# slouchpad_v1_leftpad.net
KiCad netlist of a schematic drawn in EAGLE
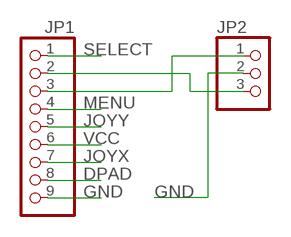
[diagram p0: schematic, sheet 1]
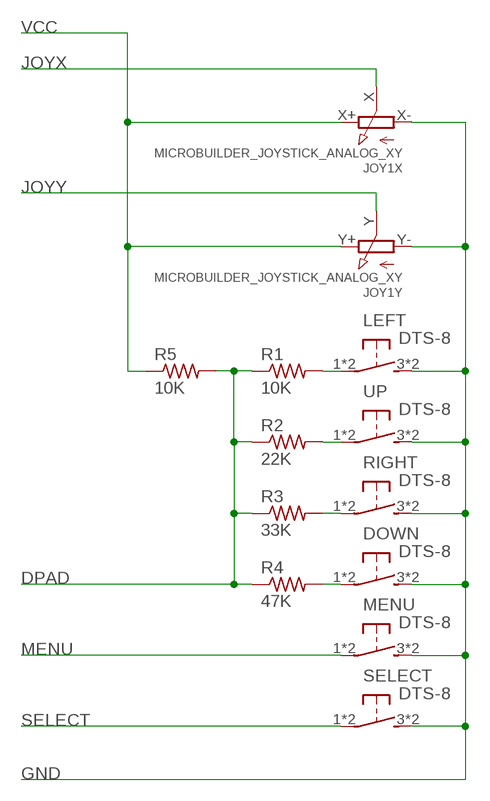
[diagram p1: schematic, sheet 2]

(export (version "E")
  (design (tool "Eeschema 10.0.6"))
  (components
    (comp (ref "DOWN")
      (value "DTS-8")
      (footprint "eagle-import:DTS-8")
      (libsource (lib "eagle-import") (part "DTS-8"))
    )
    (comp (ref "JOY1")
      (value "MICROBUILDER_JOYSTICK_ANALOG_XY")
      (footprint "eagle-import:MICROBUILDER_JOYSTICK_ANALOG_MINITHM")
      (libsource (lib "eagle-import") (part "MICROBUILDER_JOYSTICK_ANALOG_XY"))
    )
    (comp (ref "LEFT")
      (value "DTS-8")
      (footprint "eagle-import:DTS-8")
      (libsource (lib "eagle-import") (part "DTS-8"))
    )
    (comp (ref "MENU")
      (value "DTS-8")
      (footprint "eagle-import:DTS-8")
      (libsource (lib "eagle-import") (part "DTS-8"))
    )
    (comp (ref "R1")
      (value "10K")
      (footprint "eagle-import:0204_5")
      (libsource (lib "eagle-import") (part "R-US_0204/5"))
    )
    (comp (ref "R2")
      (value "22K")
      (footprint "eagle-import:0204_5")
      (libsource (lib "eagle-import") (part "R-US_0204/5"))
    )
    (comp (ref "R3")
      (value "33K")
      (footprint "eagle-import:0204_5")
      (libsource (lib "eagle-import") (part "R-US_0204/5"))
    )
    (comp (ref "R4")
      (value "47K")
      (footprint "eagle-import:0204_5")
      (libsource (lib "eagle-import") (part "R-US_0204/5"))
    )
    (comp (ref "R5")
      (value "10K")
      (footprint "eagle-import:0204_5")
      (libsource (lib "eagle-import") (part "R-US_0204/5"))
    )
    (comp (ref "RIGHT")
      (value "DTS-8")
      (footprint "eagle-import:DTS-8")
      (libsource (lib "eagle-import") (part "DTS-8"))
    )
    (comp (ref "SELECT")
      (value "DTS-8")
      (footprint "eagle-import:DTS-8")
      (libsource (lib "eagle-import") (part "DTS-8"))
    )
    (comp (ref "UP")
      (value "DTS-8")
      (footprint "eagle-import:DTS-8")
      (libsource (lib "eagle-import") (part "DTS-8"))
    )
    (comp (ref "JP1")
      (value "PINHD-1X9")
      (footprint "eagle-import:1X09")
      (libsource (lib "eagle-import") (part "PINHD-1X9"))
    )
    (comp (ref "JP2")
      (value "PINHD-1X3")
      (footprint "eagle-import:1X03")
      (libsource (lib "eagle-import") (part "PINHD-1X3"))
    )
  )
  (nets
    (net (code "1") (name "DPAD") (class "Default")
      (node (ref "JP1") (pin "8") (pinfunction "8_8") (pintype "passive"))
      (node (ref "R1") (pin "1") (pinfunction "1_1") (pintype "passive"))
      (node (ref "R2") (pin "1") (pinfunction "1_1") (pintype "passive"))
      (node (ref "R3") (pin "1") (pinfunction "1_1") (pintype "passive"))
      (node (ref "R4") (pin "1") (pinfunction "1_1") (pintype "passive"))
      (node (ref "R5") (pin "2") (pinfunction "2_2") (pintype "passive"))
    )
    (net (code "2") (name "GND") (class "Default")
      (node (ref "DOWN") (pin "3") (pinfunction "2_3") (pintype "passive"))
      (node (ref "DOWN") (pin "4") (pinfunction "2_4") (pintype "passive"))
      (node (ref "JOY1") (pin "X-") (pinfunction "A_X-") (pintype "passive"))
      (node (ref "JOY1") (pin "Y-") (pinfunction "A_Y-") (pintype "passive"))
      (node (ref "JP1") (pin "9") (pinfunction "9_9") (pintype "passive"))
      (node (ref "JP2") (pin "2") (pinfunction "2_2") (pintype "passive"))
      (node (ref "LEFT") (pin "3") (pinfunction "2_3") (pintype "passive"))
      (node (ref "LEFT") (pin "4") (pinfunction "2_4") (pintype "passive"))
      (node (ref "MENU") (pin "3") (pinfunction "2_3") (pintype "passive"))
      (node (ref "MENU") (pin "4") (pinfunction "2_4") (pintype "passive"))
      (node (ref "RIGHT") (pin "3") (pinfunction "2_3") (pintype "passive"))
      (node (ref "RIGHT") (pin "4") (pinfunction "2_4") (pintype "passive"))
      (node (ref "SELECT") (pin "3") (pinfunction "2_3") (pintype "passive"))
      (node (ref "SELECT") (pin "4") (pinfunction "2_4") (pintype "passive"))
      (node (ref "UP") (pin "3") (pinfunction "2_3") (pintype "passive"))
      (node (ref "UP") (pin "4") (pinfunction "2_4") (pintype "passive"))
    )
    (net (code "3") (name "JOYX") (class "Default")
      (node (ref "JOY1") (pin "X") (pinfunction "S_X") (pintype "passive"))
      (node (ref "JP1") (pin "7") (pinfunction "7_7") (pintype "passive"))
    )
    (net (code "4") (name "JOYY") (class "Default")
      (node (ref "JOY1") (pin "Y") (pinfunction "S_Y") (pintype "passive"))
      (node (ref "JP1") (pin "5") (pinfunction "5_5") (pintype "passive"))
    )
    (net (code "5") (name "MENU") (class "Default")
      (node (ref "JP1") (pin "4") (pinfunction "4_4") (pintype "passive"))
      (node (ref "MENU") (pin "1") (pinfunction "1_1") (pintype "passive"))
      (node (ref "MENU") (pin "2") (pinfunction "1_2") (pintype "passive"))
    )
    (net (code "6") (name "Net-(DOWN-1-Pad2)") (class "Default")
      (node (ref "DOWN") (pin "1") (pinfunction "1_1") (pintype "passive"))
      (node (ref "DOWN") (pin "2") (pinfunction "1_2") (pintype "passive"))
      (node (ref "R4") (pin "2") (pinfunction "2_2") (pintype "passive"))
    )
    (net (code "7") (name "Net-(JP1-Pad2)") (class "Default")
      (node (ref "JP1") (pin "2") (pinfunction "2_2") (pintype "passive"))
      (node (ref "JP2") (pin "3") (pinfunction "3_3") (pintype "passive"))
    )
    (net (code "8") (name "Net-(JP1-Pad3)") (class "Default")
      (node (ref "JP1") (pin "3") (pinfunction "3_3") (pintype "passive"))
      (node (ref "JP2") (pin "1") (pinfunction "1_1") (pintype "passive"))
    )
    (net (code "9") (name "Net-(LEFT-1-Pad2)") (class "Default")
      (node (ref "LEFT") (pin "1") (pinfunction "1_1") (pintype "passive"))
      (node (ref "LEFT") (pin "2") (pinfunction "1_2") (pintype "passive"))
      (node (ref "R1") (pin "2") (pinfunction "2_2") (pintype "passive"))
    )
    (net (code "10") (name "Net-(R2-Pad2)") (class "Default")
      (node (ref "R2") (pin "2") (pinfunction "2_2") (pintype "passive"))
      (node (ref "UP") (pin "1") (pinfunction "1_1") (pintype "passive"))
      (node (ref "UP") (pin "2") (pinfunction "1_2") (pintype "passive"))
    )
    (net (code "11") (name "Net-(R3-Pad2)") (class "Default")
      (node (ref "R3") (pin "2") (pinfunction "2_2") (pintype "passive"))
      (node (ref "RIGHT") (pin "1") (pinfunction "1_1") (pintype "passive"))
      (node (ref "RIGHT") (pin "2") (pinfunction "1_2") (pintype "passive"))
    )
    (net (code "12") (name "SELECT") (class "Default")
      (node (ref "JP1") (pin "1") (pinfunction "1_1") (pintype "passive"))
      (node (ref "SELECT") (pin "1") (pinfunction "1_1") (pintype "passive"))
      (node (ref "SELECT") (pin "2") (pinfunction "1_2") (pintype "passive"))
    )
    (net (code "13") (name "VCC") (class "Default")
      (node (ref "JOY1") (pin "X+") (pinfunction "E_X+") (pintype "passive"))
      (node (ref "JOY1") (pin "Y+") (pinfunction "E_Y+") (pintype "passive"))
      (node (ref "JP1") (pin "6") (pinfunction "6_6") (pintype "passive"))
      (node (ref "R5") (pin "1") (pinfunction "1_1") (pintype "passive"))
    )
  )
)
